# Power_Board.net
KiCad netlist of a schematic drawn in Altium Designer
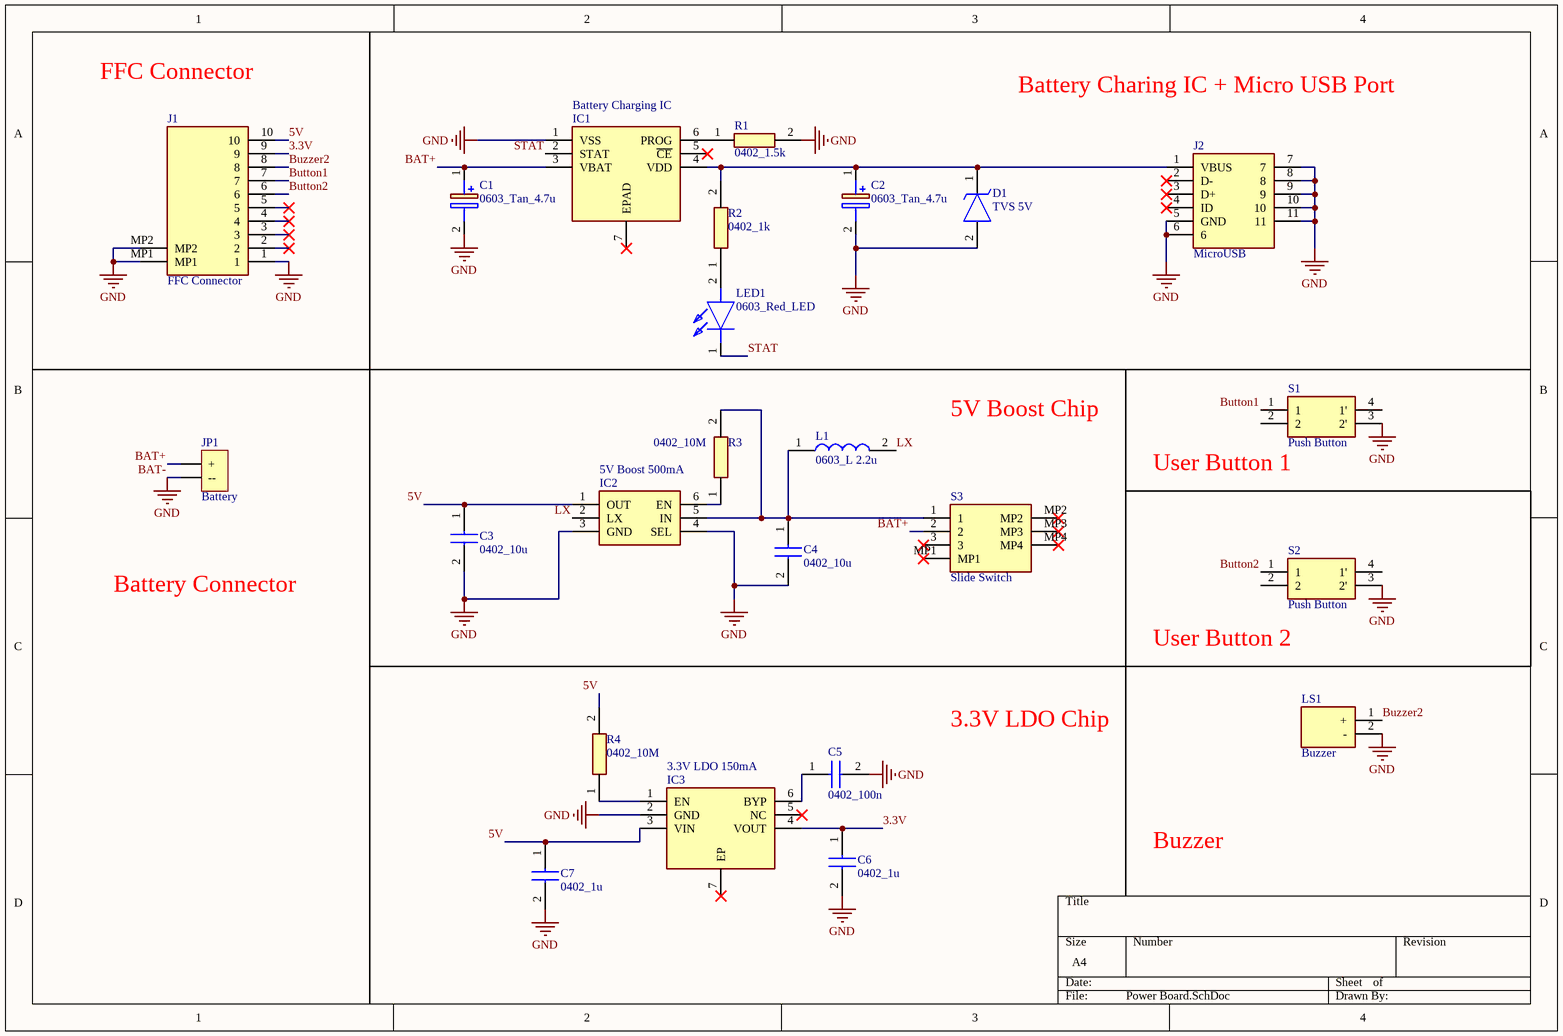
[diagram p0: Power Board.SchDoc]

(export (version "E")
  (design (tool "Eeschema 10.0.6"))
  (components
    (comp (ref "C1")
      (value "0603_Tan_4.7u")
      (footprint "SamacSys:CAPPM168X90N")
      (description "Capacitor Polarised")
      (fields (field (name "MANUFACTURER_PART_NUMBER") "TMCJ0J475MTRF"))
      (libsource (lib "Power Board SCH Lib") (part "0603_Tan_4.7u"))
    )
    (comp (ref "C2")
      (value "0603_Tan_4.7u")
      (footprint "SamacSys:CAPPM168X90N")
      (description "Capacitor Polarised")
      (fields (field (name "MANUFACTURER_PART_NUMBER") "TMCJ0J475MTRF"))
      (libsource (lib "Power Board SCH Lib") (part "0603_Tan_4.7u"))
    )
    (comp (ref "C3")
      (value "0402_10u")
      (footprint "SamacSys:CAPC1005X55N")
      (description "Capacitor")
      (fields (field (name "MANUFACTURER_PART_NUMBER") "C0402C474K8RACTU"))
      (libsource (lib "Power Board SCH Lib") (part "0402_C"))
    )
    (comp (ref "C4")
      (value "0402_10u")
      (footprint "SamacSys:CAPC1005X55N")
      (description "Capacitor")
      (fields (field (name "MANUFACTURER_PART_NUMBER") "C0402C474K8RACTU"))
      (libsource (lib "Power Board SCH Lib") (part "0402_C"))
    )
    (comp (ref "C5")
      (value "0402_100n")
      (footprint "Power Board PCB Lib:0402_CAP")
      (description "Capacitor")
      (fields (field (name "MANUFACTURER_PART_NUMBER") "VJ0603HIFRQ1KIT"))
      (libsource (lib "Power Board SCH Lib") (part "0603_C"))
    )
    (comp (ref "C6")
      (value "0402_1u")
      (footprint "SamacSys:CAPC1005X55N")
      (description "Capacitor")
      (fields (field (name "MANUFACTURER_PART_NUMBER") "C0402C474K8RACTU"))
      (libsource (lib "Power Board SCH Lib") (part "0402_C"))
    )
    (comp (ref "C7")
      (value "0402_1u")
      (footprint "SamacSys:CAPC1005X55N")
      (description "Capacitor")
      (fields (field (name "MANUFACTURER_PART_NUMBER") "C0402C474K8RACTU"))
      (libsource (lib "Power Board SCH Lib") (part "0402_C"))
    )
    (comp (ref "D1")
      (value "TVS 5V")
      (footprint "SamacSys:SODFL1006X40N")
      (description "TVS Diode (Uni-directional)")
      (fields
        (field (name "MOUSER2 PART NUMBER") "863-SZESD9101P2T5G")
        (field (name "MANUFACTURER_PART_NUMBER") "SZESD9101P2T5G")
      )
      (libsource (lib "Power Board SCH Lib") (part "TVS 5V"))
    )
    (comp (ref "IC1")
      (value "Battery Charging IC")
      (footprint "SamacSys:SON50P200X200X80-7N-D")
      (description "Integrated Circuit")
      (fields
        (field (name "MOUSER2 PART NUMBER") "579-MCP73830LT0AAIMY")
        (field (name "MANUFACTURER_PART_NUMBER") "MCP73830LT-0AAI/MYY")
      )
      (libsource (lib "Power Board SCH Lib") (part "Battery Charging IC"))
    )
    (comp (ref "IC2")
      (value "5V Boost 500mA")
      (footprint "SamacSys:SON65P200X200X80-6N")
      (description "Integrated Circuit")
      (fields (field (name "MANUFACTURER_PART_NUMBER") "MAX17223ELT+T"))
      (libsource (lib "Power Board SCH Lib") (part "5V Boost 500mA"))
    )
    (comp (ref "IC3")
      (value "3.3V LDO 150mA")
      (footprint "SamacSys:SON65P200X200X90-7N-D")
      (description "Integrated Circuit")
      (fields (field (name "MANUFACTURER_PART_NUMBER") "MIC47050-1.8YML-TR"))
      (libsource (lib "Power Board SCH Lib") (part "3.3V LDO 150mA"))
    )
    (comp (ref "J1")
      (value "FFC Connector")
      (footprint "SamacSys:528921033")
      (description "Connector")
      (fields (field (name "MANUFACTURER_PART_NUMBER") "52892-1033"))
      (libsource (lib "Power Board SCH Lib") (part "FFC Connector"))
    )
    (comp (ref "J2")
      (value "MicroUSB")
      (footprint "SamacSys:473461001")
      (description "Connector")
      (fields (field (name "MANUFACTURER_PART_NUMBER") "47346-1001"))
      (libsource (lib "Power Board SCH Lib") (part "MicroUSB"))
    )
    (comp (ref "JP1")
      (value "Battery")
      (footprint "Buzzer & Battery")
      (description "HDR-1X2")
      (fields (field (name "版权归属") "源创客"))
      (libsource (lib "Power Board SCH Lib") (part "Battery"))
    )
    (comp (ref "L1")
      (value "0603_L 2.2u")
      (footprint "Inductor")
      (description "Inductor")
      (fields (field (name "MANUFACTURER_PART_NUMBER") "PE-0603CLH2R2STS"))
      (libsource (lib "Power Board SCH Lib") (part "0603_L 2.2u"))
    )
    (comp (ref "LED1")
      (value "0603_Red_LED")
      (footprint "SamacSys:LEDC1608X80N")
      (description "LED")
      (fields (field (name "MANUFACTURER_PART_NUMBER") "150060RS75000"))
      (libsource (lib "Power Board SCH Lib") (part "0603_Red_LED"))
    )
    (comp (ref "LS1")
      (value "Buzzer")
      (footprint "Buzzer & Battery")
      (description "Loudspeaker or Buzzer")
      (fields (field (name "MANUFACTURER_PART_NUMBER") "CPT-12123-81-SMT-TR"))
      (libsource (lib "Power Board SCH Lib") (part "Buzzer"))
    )
    (comp (ref "R1")
      (value "0402_1.5k")
      (footprint "0402_R")
      (description "Resistor")
      (fields (field (name "MANUFACTURER_PART_NUMBER") "ERA-2ARB472X"))
      (libsource (lib "Power Board SCH Lib") (part "0402_R"))
    )
    (comp (ref "R2")
      (value "0402_1k")
      (footprint "0402_R")
      (description "Resistor")
      (fields (field (name "MANUFACTURER_PART_NUMBER") "ERA-2ARB472X"))
      (libsource (lib "") (part "0402_R_1"))
    )
    (comp (ref "R3")
      (value "0402_10M")
      (footprint "0402_R")
      (description "Resistor")
      (fields (field (name "MANUFACTURER_PART_NUMBER") "ERA-2ARB472X"))
      (libsource (lib "") (part "0402_R_1"))
    )
    (comp (ref "R4")
      (value "0402_10M")
      (footprint "0402_R")
      (description "Resistor")
      (fields (field (name "MANUFACTURER_PART_NUMBER") "ERA-2ARB472X"))
      (libsource (lib "") (part "0402_R_1"))
    )
    (comp (ref "S1")
      (value "Push Button")
      (footprint "Push_Button")
      (description "Switch")
      (fields
        (field (name "MOUSER2 PART NUMBER") "667-EVQ-9P701P")
        (field (name "MANUFACTURER_PART_NUMBER") "EVQ-9P701P")
      )
      (libsource (lib "Power Board SCH Lib") (part "Push Button"))
    )
    (comp (ref "S2")
      (value "Push Button")
      (footprint "Push_Button")
      (description "Switch")
      (fields
        (field (name "MOUSER2 PART NUMBER") "667-EVQ-9P701P")
        (field (name "MANUFACTURER_PART_NUMBER") "EVQ-9P701P")
      )
      (libsource (lib "Power Board SCH Lib") (part "Push Button"))
    )
    (comp (ref "S3")
      (value "Slide Switch")
      (footprint "SamacSys:450404015514")
      (description "Switch")
      (fields (field (name "MANUFACTURER_PART_NUMBER") "450404015514"))
      (libsource (lib "Power Board SCH Lib") (part "Slide Switch"))
    )
  )
  (nets
    (net (code "1") (name "/3.3V") (class "Default")
      (node (ref "C6") (pin "1") (pinfunction "1_1") (pintype "passive"))
      (node (ref "IC3") (pin "4") (pinfunction "VOUT_4") (pintype "passive"))
      (node (ref "J1") (pin "9") (pinfunction "9_9") (pintype "passive"))
    )
    (net (code "2") (name "/5V") (class "Default")
      (node (ref "C3") (pin "1") (pinfunction "1_1") (pintype "passive"))
      (node (ref "C7") (pin "1") (pinfunction "1_1") (pintype "passive"))
      (node (ref "IC2") (pin "1") (pinfunction "OUT_1") (pintype "passive"))
      (node (ref "IC3") (pin "3") (pinfunction "VIN_3") (pintype "passive"))
      (node (ref "J1") (pin "10") (pinfunction "10_10") (pintype "passive"))
      (node (ref "R4") (pin "2") (pinfunction "2_2") (pintype "passive"))
    )
    (net (code "3") (name "/BAT+") (class "Default")
      (node (ref "C1") (pin "1") (pinfunction "+_1") (pintype "passive"))
      (node (ref "IC1") (pin "3") (pinfunction "VBAT_3") (pintype "passive"))
      (node (ref "JP1") (pin "1") (pinfunction "+_1") (pintype "passive"))
      (node (ref "S3") (pin "2") (pinfunction "2_2") (pintype "passive"))
    )
    (net (code "4") (name "/Button1") (class "Default")
      (node (ref "J1") (pin "7") (pinfunction "7_7") (pintype "passive"))
      (node (ref "S1") (pin "1") (pinfunction "1_1") (pintype "passive"))
    )
    (net (code "5") (name "/Button2") (class "Default")
      (node (ref "J1") (pin "6") (pinfunction "6_6") (pintype "passive"))
      (node (ref "S2") (pin "1") (pinfunction "1_1") (pintype "passive"))
    )
    (net (code "6") (name "/Buzzer2") (class "Default")
      (node (ref "J1") (pin "8") (pinfunction "8_8") (pintype "passive"))
      (node (ref "LS1") (pin "1") (pinfunction "+_1") (pintype "passive"))
    )
    (net (code "7") (name "/LX") (class "Default")
      (node (ref "IC2") (pin "2") (pinfunction "LX_2") (pintype "passive"))
      (node (ref "L1") (pin "2") (pinfunction "2_2") (pintype "passive"))
    )
    (net (code "8") (name "/STAT") (class "Default")
      (node (ref "IC1") (pin "2") (pinfunction "STAT_2") (pintype "passive"))
      (node (ref "LED1") (pin "1") (pinfunction "K_1") (pintype "passive"))
    )
    (net (code "9") (name "GND") (class "Default")
      (node (ref "C1") (pin "2") (pinfunction "-_2") (pintype "passive"))
      (node (ref "C2") (pin "2") (pinfunction "-_2") (pintype "passive"))
      (node (ref "C3") (pin "2") (pinfunction "2_2") (pintype "passive"))
      (node (ref "C4") (pin "2") (pinfunction "2_2") (pintype "passive"))
      (node (ref "C5") (pin "2") (pinfunction "2_2") (pintype "passive"))
      (node (ref "C6") (pin "2") (pinfunction "2_2") (pintype "passive"))
      (node (ref "C7") (pin "2") (pinfunction "2_2") (pintype "passive"))
      (node (ref "D1") (pin "2") (pinfunction "A_2") (pintype "passive"))
      (node (ref "IC1") (pin "1") (pinfunction "VSS_1") (pintype "passive"))
      (node (ref "IC2") (pin "3") (pinfunction "GND_3") (pintype "passive"))
      (node (ref "IC2") (pin "4") (pinfunction "SEL_4") (pintype "passive"))
      (node (ref "IC3") (pin "2") (pinfunction "GND_2") (pintype "passive"))
      (node (ref "J1") (pin "1") (pinfunction "1_1") (pintype "passive"))
      (node (ref "J1") (pin "MP1") (pinfunction "MP1_MP1") (pintype "passive"))
      (node (ref "J1") (pin "MP2") (pinfunction "MP2_MP2") (pintype "passive"))
      (node (ref "J2") (pin "10") (pinfunction "10_10") (pintype "passive"))
      (node (ref "J2") (pin "11") (pinfunction "11_11") (pintype "passive"))
      (node (ref "J2") (pin "5") (pinfunction "GND_5") (pintype "passive"))
      (node (ref "J2") (pin "6") (pinfunction "6_6") (pintype "passive"))
      (node (ref "J2") (pin "7") (pinfunction "7_7") (pintype "passive"))
      (node (ref "J2") (pin "8") (pinfunction "8_8") (pintype "passive"))
      (node (ref "J2") (pin "9") (pinfunction "9_9") (pintype "passive"))
      (node (ref "JP1") (pin "2") (pinfunction "--_2") (pintype "passive"))
      (node (ref "LS1") (pin "2") (pinfunction "-_2") (pintype "passive"))
      (node (ref "R1") (pin "2") (pinfunction "2_2") (pintype "passive"))
      (node (ref "S1") (pin "3") (pinfunction "2'_3") (pintype "passive"))
      (node (ref "S2") (pin "3") (pinfunction "2'_3") (pintype "passive"))
    )
    (net (code "10") (name "Net-(C2-+)") (class "Default")
      (node (ref "C2") (pin "1") (pinfunction "+_1") (pintype "passive"))
      (node (ref "D1") (pin "1") (pinfunction "K_1") (pintype "passive"))
      (node (ref "IC1") (pin "4") (pinfunction "VDD_4") (pintype "passive"))
      (node (ref "J2") (pin "1") (pinfunction "VBUS_1") (pintype "passive"))
      (node (ref "R2") (pin "2") (pinfunction "2_2") (pintype "passive"))
    )
    (net (code "11") (name "Net-(IC1-PROG)") (class "Default")
      (node (ref "IC1") (pin "6") (pinfunction "PROG_6") (pintype "passive"))
      (node (ref "R1") (pin "1") (pinfunction "1_1") (pintype "passive"))
    )
    (net (code "12") (name "Net-(IC2-EN)") (class "Default")
      (node (ref "IC2") (pin "6") (pinfunction "EN_6") (pintype "passive"))
      (node (ref "R3") (pin "1") (pinfunction "1_1") (pintype "passive"))
    )
    (net (code "13") (name "Net-(IC2-IN)") (class "Default")
      (node (ref "C4") (pin "1") (pinfunction "1_1") (pintype "passive"))
      (node (ref "IC2") (pin "5") (pinfunction "IN_5") (pintype "passive"))
      (node (ref "L1") (pin "1") (pinfunction "1_1") (pintype "passive"))
      (node (ref "R3") (pin "2") (pinfunction "2_2") (pintype "passive"))
      (node (ref "S3") (pin "1") (pinfunction "1_1") (pintype "passive"))
    )
    (net (code "14") (name "Net-(IC3-BYP)") (class "Default")
      (node (ref "C5") (pin "1") (pinfunction "1_1") (pintype "passive"))
      (node (ref "IC3") (pin "6") (pinfunction "BYP_6") (pintype "passive"))
    )
    (net (code "15") (name "Net-(IC3-EN)") (class "Default")
      (node (ref "IC3") (pin "1") (pinfunction "EN_1") (pintype "passive"))
      (node (ref "R4") (pin "1") (pinfunction "1_1") (pintype "passive"))
    )
    (net (code "16") (name "Net-(LED1-A)") (class "Default")
      (node (ref "LED1") (pin "2") (pinfunction "A_2") (pintype "passive"))
      (node (ref "R2") (pin "1") (pinfunction "1_1") (pintype "passive"))
    )
    (net (code "17") (name "unconnected-(IC1-EPAD-Pad7)") (class "Default")
      (node (ref "IC1") (pin "7") (pinfunction "EPAD_7") (pintype "passive+no_connect"))
    )
    (net (code "18") (name "unconnected-(IC1-~{CE}-Pad5)") (class "Default")
      (node (ref "IC1") (pin "5") (pinfunction "~{CE}_5") (pintype "passive+no_connect"))
    )
    (net (code "19") (name "unconnected-(IC3-EP-Pad7)") (class "Default")
      (node (ref "IC3") (pin "7") (pinfunction "EP_7") (pintype "passive+no_connect"))
    )
    (net (code "20") (name "unconnected-(IC3-NC-Pad5)") (class "Default")
      (node (ref "IC3") (pin "5") (pinfunction "NC_5") (pintype "passive+no_connect"))
    )
    (net (code "21") (name "unconnected-(J1-Pad2)") (class "Default")
      (node (ref "J1") (pin "2") (pinfunction "2_2") (pintype "passive+no_connect"))
    )
    (net (code "22") (name "unconnected-(J1-Pad3)") (class "Default")
      (node (ref "J1") (pin "3") (pinfunction "3_3") (pintype "passive+no_connect"))
    )
    (net (code "23") (name "unconnected-(J1-Pad4)") (class "Default")
      (node (ref "J1") (pin "4") (pinfunction "4_4") (pintype "passive+no_connect"))
    )
    (net (code "24") (name "unconnected-(J1-Pad5)") (class "Default")
      (node (ref "J1") (pin "5") (pinfunction "5_5") (pintype "passive+no_connect"))
    )
    (net (code "25") (name "unconnected-(J2-D+-Pad3)") (class "Default")
      (node (ref "J2") (pin "3") (pinfunction "D+_3") (pintype "passive+no_connect"))
    )
    (net (code "26") (name "unconnected-(J2-D--Pad2)") (class "Default")
      (node (ref "J2") (pin "2") (pinfunction "D-_2") (pintype "passive+no_connect"))
    )
    (net (code "27") (name "unconnected-(J2-ID-Pad4)") (class "Default")
      (node (ref "J2") (pin "4") (pinfunction "ID_4") (pintype "passive+no_connect"))
    )
    (net (code "28") (name "unconnected-(S1-1'-Pad4)") (class "Default")
      (node (ref "S1") (pin "4") (pinfunction "1'_4") (pintype "passive"))
    )
    (net (code "29") (name "unconnected-(S1-Pad2)") (class "Default")
      (node (ref "S1") (pin "2") (pinfunction "2_2") (pintype "passive"))
    )
    (net (code "30") (name "unconnected-(S2-1'-Pad4)") (class "Default")
      (node (ref "S2") (pin "4") (pinfunction "1'_4") (pintype "passive"))
    )
    (net (code "31") (name "unconnected-(S2-Pad2)") (class "Default")
      (node (ref "S2") (pin "2") (pinfunction "2_2") (pintype "passive"))
    )
    (net (code "32") (name "unconnected-(S3-Pad3)") (class "Default")
      (node (ref "S3") (pin "3") (pinfunction "3_3") (pintype "passive+no_connect"))
    )
    (net (code "33") (name "unconnected-(S3-PadMP1)") (class "Default")
      (node (ref "S3") (pin "MP1") (pinfunction "MP1_MP1") (pintype "passive+no_connect"))
    )
    (net (code "34") (name "unconnected-(S3-PadMP2)") (class "Default")
      (node (ref "S3") (pin "MP2") (pinfunction "MP2_MP2") (pintype "passive+no_connect"))
    )
    (net (code "35") (name "unconnected-(S3-PadMP3)") (class "Default")
      (node (ref "S3") (pin "MP3") (pinfunction "MP3_MP3") (pintype "passive+no_connect"))
    )
    (net (code "36") (name "unconnected-(S3-PadMP4)") (class "Default")
      (node (ref "S3") (pin "MP4") (pinfunction "MP4_MP4") (pintype "passive+no_connect"))
    )
  )
)
